# Sheet2.net
KiCad netlist of a schematic drawn in Altium Designer
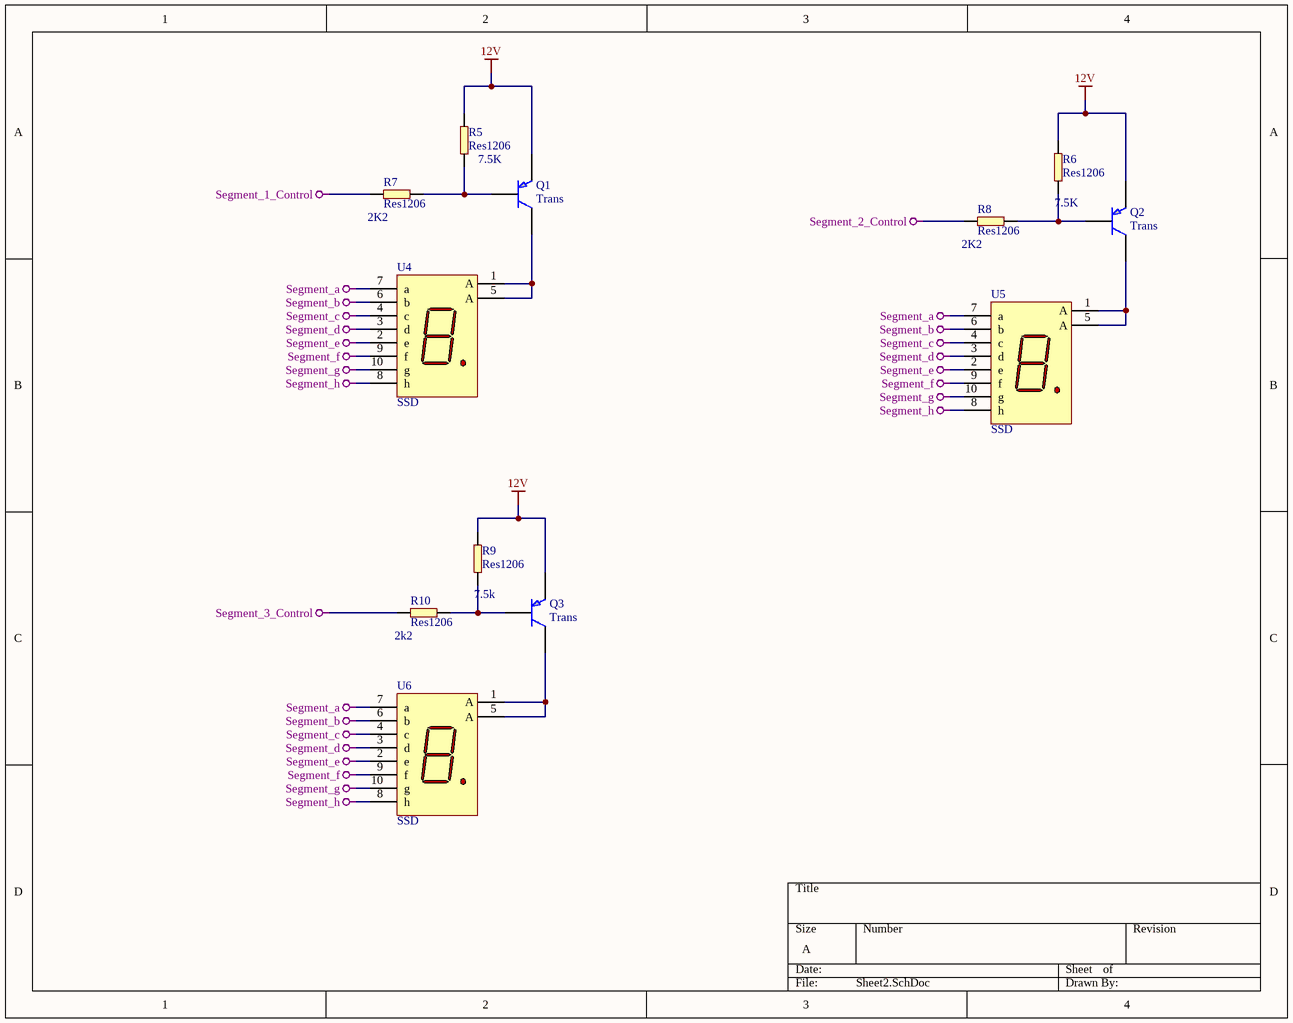
[diagram p0: Sheet2.SchDoc]

(export (version "E")
  (design (tool "Eeschema 10.0.6"))
  (components
    (comp (ref "Q1")
      (value "Trans")
      (footprint "2N6107")
      (description "pnp transistor")
      (libsource (lib "VIJAYIntegrated_Library") (part "2N6107"))
    )
    (comp (ref "Q2")
      (value "Trans")
      (footprint "2N6107")
      (description "pnp transistor")
      (libsource (lib "VIJAYIntegrated_Library") (part "2N6107"))
    )
    (comp (ref "Q3")
      (value "Trans")
      (footprint "2N6107")
      (description "pnp transistor")
      (libsource (lib "VIJAYIntegrated_Library") (part "2N6107"))
    )
    (comp (ref "R5")
      (value "Res1206")
      (footprint "1206")
      (fields (field (name "ALTIUM_VALUE") "7.5K"))
      (libsource (lib "") (part "Res1206_2"))
    )
    (comp (ref "R6")
      (value "Res1206")
      (footprint "1206")
      (fields (field (name "ALTIUM_VALUE") "7.5K"))
      (libsource (lib "") (part "Res1206_1"))
    )
    (comp (ref "R7")
      (value "Res1206")
      (footprint "1206")
      (fields (field (name "ALTIUM_VALUE") "2K2"))
      (libsource (lib "") (part "Res1206_3"))
    )
    (comp (ref "R8")
      (value "Res1206")
      (footprint "1206")
      (fields (field (name "ALTIUM_VALUE") "2K2"))
      (libsource (lib "Dinesh_New_Integrated_Library") (part "Res1206"))
    )
    (comp (ref "R9")
      (value "Res1206")
      (footprint "1206")
      (fields (field (name "ALTIUM_VALUE") "7.5k"))
      (libsource (lib "") (part "Res1206_1"))
    )
    (comp (ref "R10")
      (value "Res1206")
      (footprint "1206")
      (fields (field (name "ALTIUM_VALUE") "2k2"))
      (libsource (lib "Dinesh_New_Integrated_Library") (part "Res1206"))
    )
    (comp (ref "U4")
      (value "SSD")
      (footprint "SP1802_SSD")
      (description "SSD 48MM")
      (libsource (lib "VIJAYIntegrated_Library") (part "SP1802"))
    )
    (comp (ref "U5")
      (value "SSD")
      (footprint "SP1802_SSD")
      (description "SSD 48MM")
      (libsource (lib "VIJAYIntegrated_Library") (part "SP1802"))
    )
    (comp (ref "U6")
      (value "SSD")
      (footprint "SP1802_SSD")
      (description "SSD 48MM")
      (libsource (lib "VIJAYIntegrated_Library") (part "SP1802"))
    )
  )
  (nets
    (net (code "1") (name "12V") (class "Default")
      (node (ref "Q1") (pin "3") (pinfunction "E_3") (pintype "passive"))
      (node (ref "Q2") (pin "3") (pinfunction "E_3") (pintype "passive"))
      (node (ref "Q3") (pin "3") (pinfunction "E_3") (pintype "passive"))
      (node (ref "R5") (pin "1") (pinfunction "a_1") (pintype "passive"))
      (node (ref "R6") (pin "2") (pinfunction "b_2") (pintype "passive"))
      (node (ref "R9") (pin "2") (pinfunction "b_2") (pintype "passive"))
    )
    (net (code "2") (name "Net-(Q1-B)") (class "Default")
      (node (ref "Q1") (pin "1") (pinfunction "B_1") (pintype "passive"))
      (node (ref "R5") (pin "2") (pinfunction "b_2") (pintype "passive"))
      (node (ref "R7") (pin "1") (pinfunction "a_1") (pintype "passive"))
    )
    (net (code "3") (name "Net-(Q1-C)") (class "Default")
      (node (ref "Q1") (pin "2") (pinfunction "C_2") (pintype "passive"))
      (node (ref "U4") (pin "1") (pinfunction "A_1") (pintype "passive"))
      (node (ref "U4") (pin "5") (pinfunction "A_5") (pintype "passive"))
    )
    (net (code "4") (name "Net-(Q2-B)") (class "Default")
      (node (ref "Q2") (pin "1") (pinfunction "B_1") (pintype "passive"))
      (node (ref "R6") (pin "1") (pinfunction "a_1") (pintype "passive"))
      (node (ref "R8") (pin "2") (pinfunction "b_2") (pintype "passive"))
    )
    (net (code "5") (name "Net-(Q2-C)") (class "Default")
      (node (ref "Q2") (pin "2") (pinfunction "C_2") (pintype "passive"))
      (node (ref "U5") (pin "1") (pinfunction "A_1") (pintype "passive"))
      (node (ref "U5") (pin "5") (pinfunction "A_5") (pintype "passive"))
    )
    (net (code "6") (name "Net-(Q3-B)") (class "Default")
      (node (ref "Q3") (pin "1") (pinfunction "B_1") (pintype "passive"))
      (node (ref "R10") (pin "2") (pinfunction "b_2") (pintype "passive"))
      (node (ref "R9") (pin "1") (pinfunction "a_1") (pintype "passive"))
    )
    (net (code "7") (name "Net-(Q3-C)") (class "Default")
      (node (ref "Q3") (pin "2") (pinfunction "C_2") (pintype "passive"))
      (node (ref "U6") (pin "1") (pinfunction "A_1") (pintype "passive"))
      (node (ref "U6") (pin "5") (pinfunction "A_5") (pintype "passive"))
    )
    (net (code "8") (name "Segment_1_Control") (class "Default")
      (node (ref "R7") (pin "2") (pinfunction "b_2") (pintype "passive"))
    )
    (net (code "9") (name "Segment_2_Control") (class "Default")
      (node (ref "R8") (pin "1") (pinfunction "a_1") (pintype "passive"))
    )
    (net (code "10") (name "Segment_3_Control") (class "Default")
      (node (ref "R10") (pin "1") (pinfunction "a_1") (pintype "passive"))
    )
    (net (code "11") (name "Segment_a") (class "Default")
      (node (ref "U4") (pin "7") (pinfunction "a_7") (pintype "passive"))
      (node (ref "U5") (pin "7") (pinfunction "a_7") (pintype "passive"))
      (node (ref "U6") (pin "7") (pinfunction "a_7") (pintype "passive"))
    )
    (net (code "12") (name "Segment_b") (class "Default")
      (node (ref "U4") (pin "6") (pinfunction "b_6") (pintype "passive"))
      (node (ref "U5") (pin "6") (pinfunction "b_6") (pintype "passive"))
      (node (ref "U6") (pin "6") (pinfunction "b_6") (pintype "passive"))
    )
    (net (code "13") (name "Segment_c") (class "Default")
      (node (ref "U4") (pin "4") (pinfunction "c_4") (pintype "passive"))
      (node (ref "U5") (pin "4") (pinfunction "c_4") (pintype "passive"))
      (node (ref "U6") (pin "4") (pinfunction "c_4") (pintype "passive"))
    )
    (net (code "14") (name "Segment_d") (class "Default")
      (node (ref "U4") (pin "3") (pinfunction "d_3") (pintype "passive"))
      (node (ref "U5") (pin "3") (pinfunction "d_3") (pintype "passive"))
      (node (ref "U6") (pin "3") (pinfunction "d_3") (pintype "passive"))
    )
    (net (code "15") (name "Segment_e") (class "Default")
      (node (ref "U4") (pin "2") (pinfunction "e_2") (pintype "passive"))
      (node (ref "U5") (pin "2") (pinfunction "e_2") (pintype "passive"))
      (node (ref "U6") (pin "2") (pinfunction "e_2") (pintype "passive"))
    )
    (net (code "16") (name "Segment_f") (class "Default")
      (node (ref "U4") (pin "9") (pinfunction "f_9") (pintype "passive"))
      (node (ref "U5") (pin "9") (pinfunction "f_9") (pintype "passive"))
      (node (ref "U6") (pin "9") (pinfunction "f_9") (pintype "passive"))
    )
    (net (code "17") (name "Segment_g") (class "Default")
      (node (ref "U4") (pin "10") (pinfunction "g_10") (pintype "passive"))
      (node (ref "U5") (pin "10") (pinfunction "g_10") (pintype "passive"))
      (node (ref "U6") (pin "10") (pinfunction "g_10") (pintype "passive"))
    )
    (net (code "18") (name "Segment_h") (class "Default")
      (node (ref "U4") (pin "8") (pinfunction "h_8") (pintype "passive"))
      (node (ref "U5") (pin "8") (pinfunction "h_8") (pintype "passive"))
      (node (ref "U6") (pin "8") (pinfunction "h_8") (pintype "passive"))
    )
  )
)
